# SCH_Proyecto-1_2025-03-27.net
KiCad netlist of a schematic drawn in EasyEDA
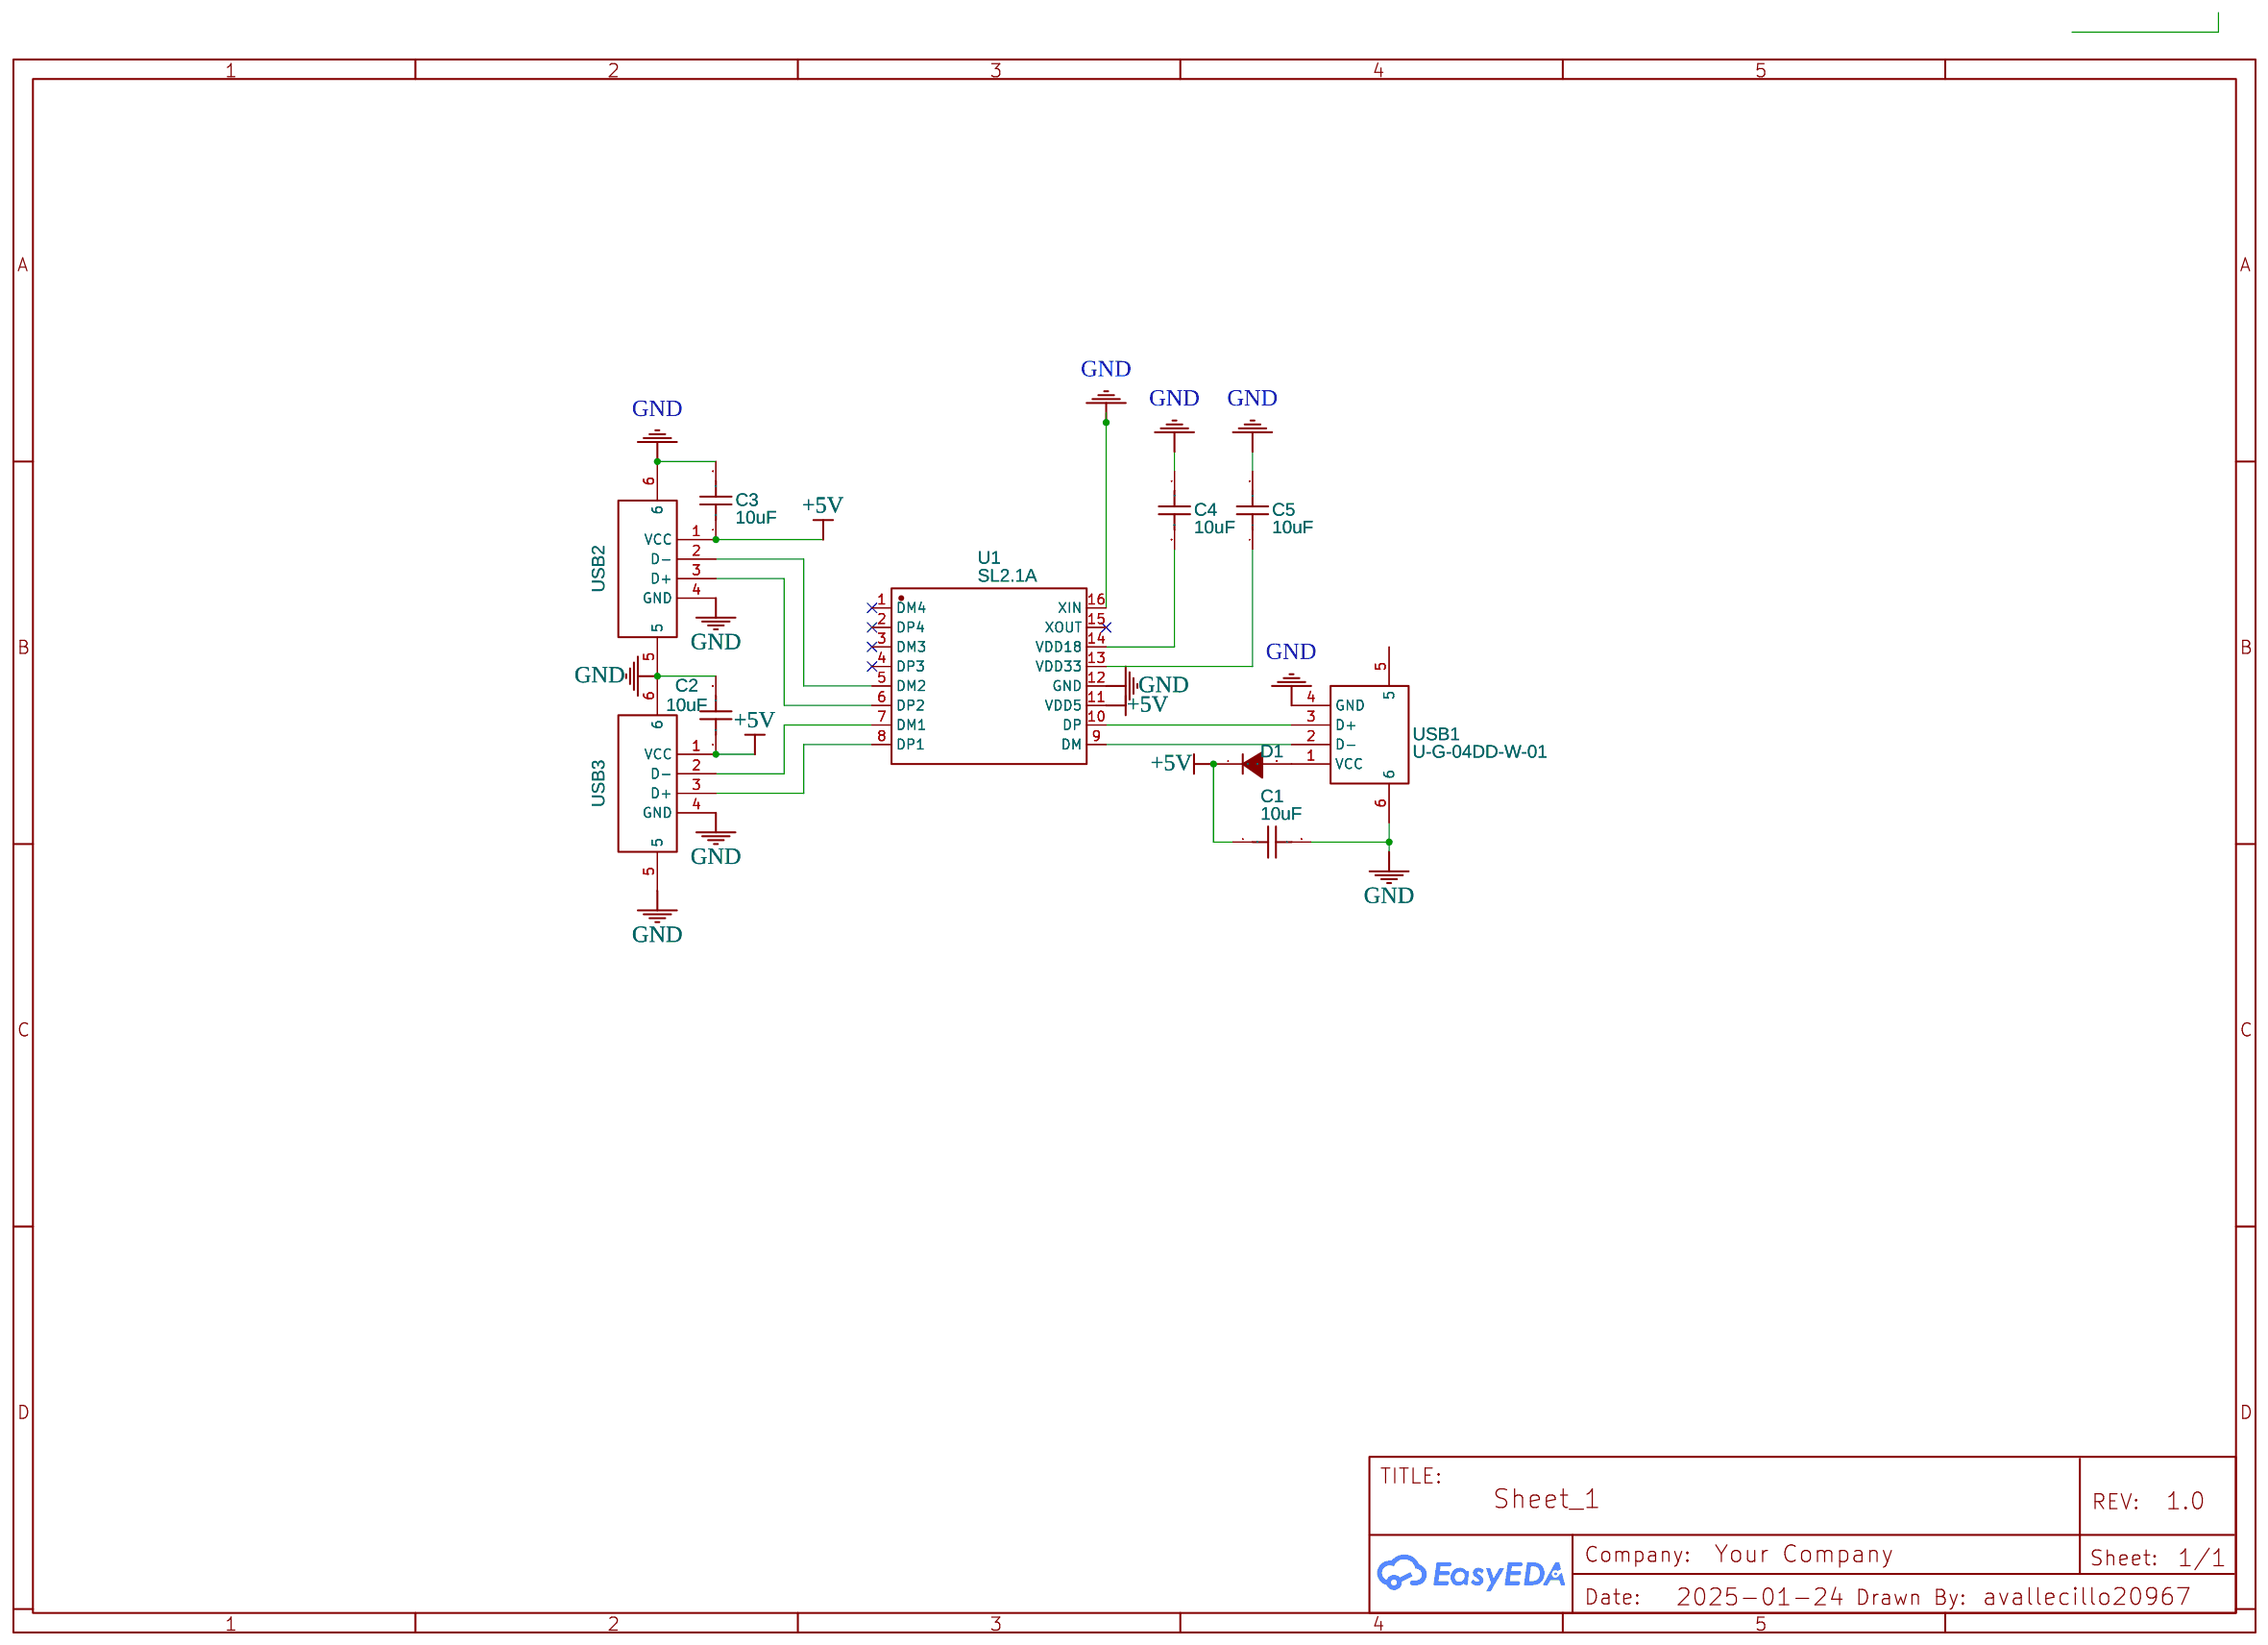
[diagram p0: schematic sheet]

(export (version "E")
  (design (tool "Eeschema 10.0.6"))
  (components
    (comp (ref "C1")
      (value "10uF")
      (fields
        (field (name "Manufacturer Part") "CL10A106KP8NNNC")
        (field (name "Manufacturer") "SAMSUNG(三星)")
      )
      (libsource (lib "") (part "CL10A106KP8NNNC_1"))
    )
    (comp (ref "C2")
      (value "10uF")
      (fields
        (field (name "Manufacturer Part") "CL10A106KP8NNNC")
        (field (name "Manufacturer") "SAMSUNG(三星)")
      )
      (libsource (lib "") (part "CL10A106KP8NNNC"))
    )
    (comp (ref "C3")
      (value "10uF")
      (fields
        (field (name "Manufacturer Part") "CL10A106KP8NNNC")
        (field (name "Manufacturer") "SAMSUNG(三星)")
      )
      (libsource (lib "") (part "CL10A106KP8NNNC"))
    )
    (comp (ref "C4")
      (value "10uF")
      (fields
        (field (name "Manufacturer Part") "CL10A106KP8NNNC")
        (field (name "Manufacturer") "SAMSUNG(三星)")
      )
      (libsource (lib "") (part "CL10A106KP8NNNC_2"))
    )
    (comp (ref "C5")
      (value "10uF")
      (fields
        (field (name "Manufacturer Part") "CL10A106KP8NNNC")
        (field (name "Manufacturer") "SAMSUNG(三星)")
      )
      (libsource (lib "") (part "CL10A106KP8NNNC"))
    )
    (comp (ref "D1")
      (value "NSR0320MW2T1G")
      (fields (field (name "Manufacturer") "onsemi(安森美)"))
      (libsource (lib "") (part "NSR0320MW2T1G"))
    )
    (comp (ref "U1")
      (value "SL2.1A")
      (fields (field (name "Manufacturer") "CoreChips(和芯润德)"))
      (libsource (lib "") (part "SL2.1A"))
    )
    (comp (ref "USB1")
      (value "U-G-04DD-W-01")
      (fields (field (name "Manufacturer Part") "U-G-O4DD-W-1") (field (name "Manufacturer") "韩国韩荣"))
      (libsource (lib "") (part "U-G-04DD-W-01"))
    )
    (comp (ref "USB2")
      (value "USB-AF-90-14.4X13.6-H7.0-DIP")
      (fields (field (name "Manufacturer Part") "903-131A1011D10100") (field (name "Manufacturer") "精拓金"))
      (libsource (lib "") (part "USB-AF-90-14.4X13.6-H7.0-DIP"))
    )
    (comp (ref "USB3")
      (value "USB-AF-90-14.4X13.6-H7.0-DIP")
      (fields (field (name "Manufacturer Part") "903-131A1011D10100") (field (name "Manufacturer") "精拓金"))
      (libsource (lib "") (part "USB-AF-90-14.4X13.6-H7.0-DIP"))
    )
  )
  (nets
    (net (code "1") (name "+5V") (class "Default")
      (node (ref "C1") (pin "1") (pinfunction "1_1") (pintype "unspecified"))
      (node (ref "C2") (pin "1") (pinfunction "1_1") (pintype "unspecified"))
      (node (ref "C3") (pin "1") (pinfunction "1_1") (pintype "unspecified"))
      (node (ref "D1") (pin "1") (pinfunction "C_1") (pintype "unspecified"))
      (node (ref "U1") (pin "11") (pinfunction "VDD5_11") (pintype "unspecified"))
      (node (ref "USB2") (pin "1") (pinfunction "VCC_1") (pintype "unspecified"))
      (node (ref "USB3") (pin "1") (pinfunction "VCC_1") (pintype "unspecified"))
    )
    (net (code "2") (name "GND") (class "Default")
      (node (ref "C1") (pin "2") (pinfunction "2_2") (pintype "unspecified"))
      (node (ref "C2") (pin "2") (pinfunction "2_2") (pintype "unspecified"))
      (node (ref "C3") (pin "2") (pinfunction "2_2") (pintype "unspecified"))
      (node (ref "C4") (pin "1") (pinfunction "1_1") (pintype "unspecified"))
      (node (ref "C5") (pin "2") (pinfunction "2_2") (pintype "unspecified"))
      (node (ref "U1") (pin "12") (pinfunction "GND_12") (pintype "unspecified"))
      (node (ref "U1") (pin "16") (pinfunction "XIN_16") (pintype "unspecified"))
      (node (ref "USB1") (pin "4") (pinfunction "GND_4") (pintype "unspecified"))
      (node (ref "USB1") (pin "6") (pinfunction "6_6") (pintype "unspecified"))
      (node (ref "USB2") (pin "4") (pinfunction "GND_4") (pintype "unspecified"))
      (node (ref "USB2") (pin "5") (pinfunction "5_5") (pintype "unspecified"))
      (node (ref "USB2") (pin "6") (pinfunction "6_6") (pintype "unspecified"))
      (node (ref "USB3") (pin "4") (pinfunction "GND_4") (pintype "unspecified"))
      (node (ref "USB3") (pin "5") (pinfunction "5_5") (pintype "unspecified"))
      (node (ref "USB3") (pin "6") (pinfunction "6_6") (pintype "unspecified"))
    )
    (net (code "3") (name "Net-(D1-A)") (class "Default")
      (node (ref "D1") (pin "2") (pinfunction "A_2") (pintype "unspecified"))
      (node (ref "USB1") (pin "1") (pinfunction "VCC_1") (pintype "unspecified"))
    )
    (net (code "4") (name "Net-(U1-DM)") (class "Default")
      (node (ref "U1") (pin "9") (pinfunction "DM_9") (pintype "unspecified"))
      (node (ref "USB1") (pin "2") (pinfunction "D-_2") (pintype "unspecified"))
    )
    (net (code "5") (name "Net-(U1-DM1)") (class "Default")
      (node (ref "U1") (pin "7") (pinfunction "DM1_7") (pintype "unspecified"))
      (node (ref "USB3") (pin "2") (pinfunction "D-_2") (pintype "unspecified"))
    )
    (net (code "6") (name "Net-(U1-DM2)") (class "Default")
      (node (ref "U1") (pin "5") (pinfunction "DM2_5") (pintype "unspecified"))
      (node (ref "USB2") (pin "2") (pinfunction "D-_2") (pintype "unspecified"))
    )
    (net (code "7") (name "Net-(U1-DP)") (class "Default")
      (node (ref "U1") (pin "10") (pinfunction "DP_10") (pintype "unspecified"))
      (node (ref "USB1") (pin "3") (pinfunction "D+_3") (pintype "unspecified"))
    )
    (net (code "8") (name "Net-(U1-DP1)") (class "Default")
      (node (ref "U1") (pin "8") (pinfunction "DP1_8") (pintype "unspecified"))
      (node (ref "USB3") (pin "3") (pinfunction "D+_3") (pintype "unspecified"))
    )
    (net (code "9") (name "Net-(U1-DP2)") (class "Default")
      (node (ref "U1") (pin "6") (pinfunction "DP2_6") (pintype "unspecified"))
      (node (ref "USB2") (pin "3") (pinfunction "D+_3") (pintype "unspecified"))
    )
    (net (code "10") (name "Net-(U1-VDD18)") (class "Default")
      (node (ref "C4") (pin "2") (pinfunction "2_2") (pintype "unspecified"))
      (node (ref "U1") (pin "14") (pinfunction "VDD18_14") (pintype "unspecified"))
    )
    (net (code "11") (name "Net-(U1-VDD33)") (class "Default")
      (node (ref "C5") (pin "1") (pinfunction "1_1") (pintype "unspecified"))
      (node (ref "U1") (pin "13") (pinfunction "VDD33_13") (pintype "unspecified"))
    )
    (net (code "12") (name "unconnected-(U1-DM3-Pad3)") (class "Default")
      (node (ref "U1") (pin "3") (pinfunction "DM3_3") (pintype "unspecified+no_connect"))
    )
    (net (code "13") (name "unconnected-(U1-DM4-Pad1)") (class "Default")
      (node (ref "U1") (pin "1") (pinfunction "DM4_1") (pintype "unspecified+no_connect"))
    )
    (net (code "14") (name "unconnected-(U1-DP3-Pad4)") (class "Default")
      (node (ref "U1") (pin "4") (pinfunction "DP3_4") (pintype "unspecified+no_connect"))
    )
    (net (code "15") (name "unconnected-(U1-DP4-Pad2)") (class "Default")
      (node (ref "U1") (pin "2") (pinfunction "DP4_2") (pintype "unspecified+no_connect"))
    )
    (net (code "16") (name "unconnected-(U1-XOUT-Pad15)") (class "Default")
      (node (ref "U1") (pin "15") (pinfunction "XOUT_15") (pintype "unspecified+no_connect"))
    )
    (net (code "17") (name "unconnected-(USB1-Pad5)") (class "Default")
      (node (ref "USB1") (pin "5") (pinfunction "5_5") (pintype "unspecified"))
    )
  )
)
